# mainBoardV1.net
KiCad netlist of a schematic drawn in EAGLE
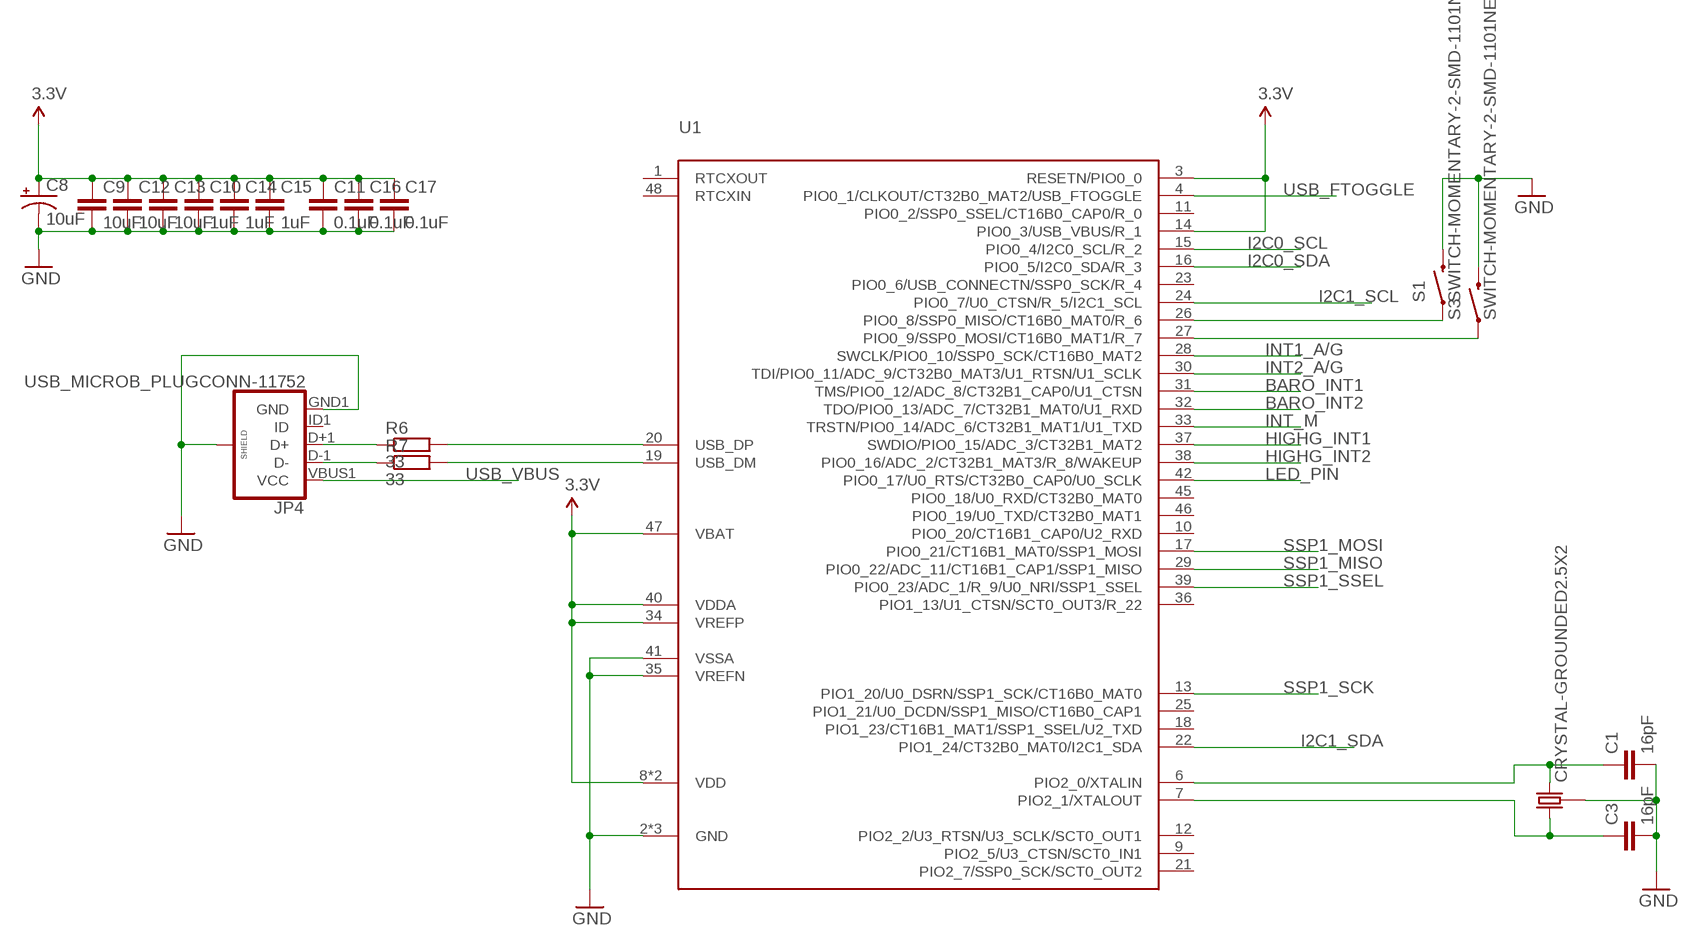
[diagram p0: schematic, sheet 1]
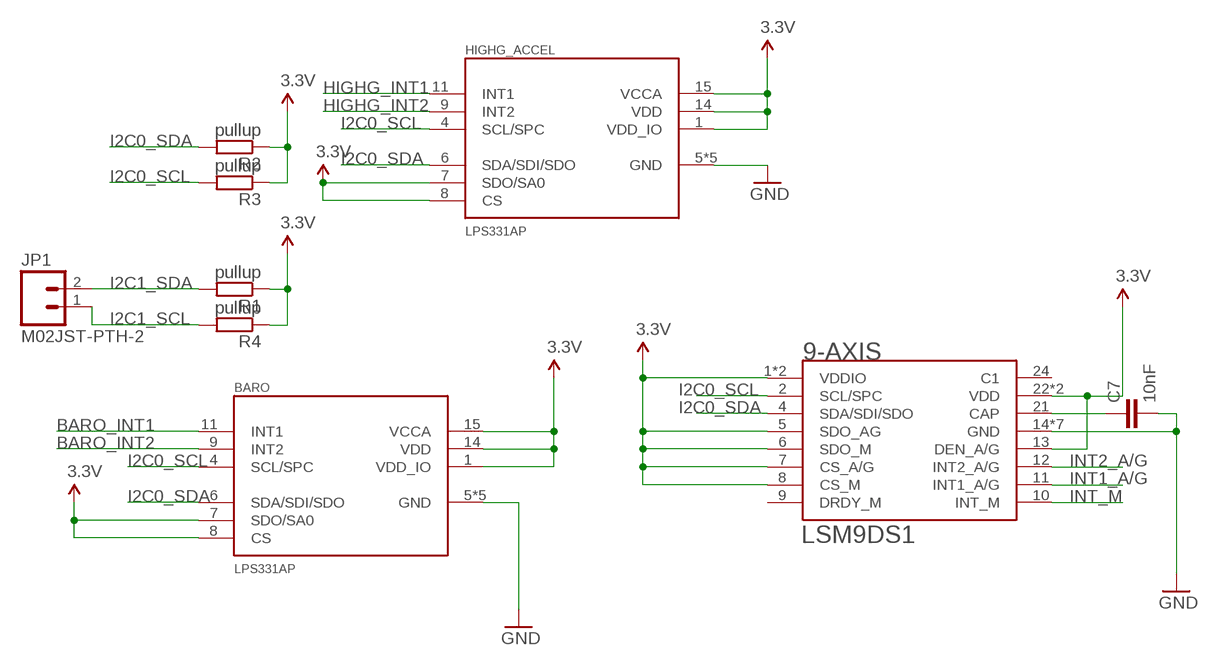
[diagram p1: schematic, sheet 2]
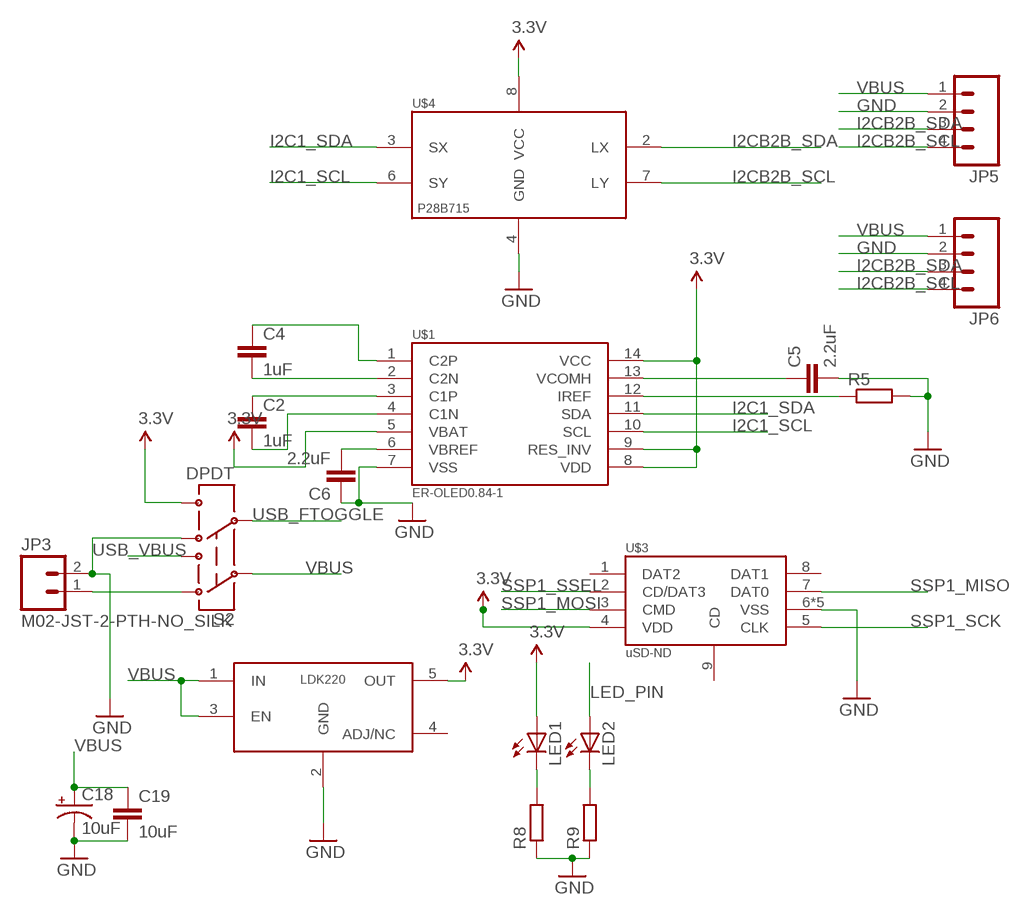
[diagram p2: schematic, sheet 3]

(export (version "E")
  (design (tool "Eeschema 10.0.6"))
  (components
    (comp (ref "C2")
      (value "1uF")
      (footprint "eagle-import:C0402")
      (libsource (lib "eagle-import") (part "C0402"))
    )
    (comp (ref "C4")
      (value "1uF")
      (footprint "eagle-import:C0402")
      (libsource (lib "eagle-import") (part "C0402"))
    )
    (comp (ref "C5")
      (value "2.2uF")
      (footprint "eagle-import:C0402")
      (libsource (lib "eagle-import") (part "C0402"))
    )
    (comp (ref "C6")
      (value "2.2uF")
      (footprint "eagle-import:C0402")
      (libsource (lib "eagle-import") (part "C0402"))
    )
    (comp (ref "C18")
      (value "10uF")
      (footprint "eagle-import:CT3216")
      (libsource (lib "eagle-import") (part "CPOL1206"))
    )
    (comp (ref "C19")
      (value "10uF")
      (footprint "eagle-import:C0402")
      (libsource (lib "eagle-import") (part "C0402"))
    )
    (comp (ref "JP3")
      (value "M02-JST-2-PTH-NO_SILK")
      (footprint "eagle-import:JST-2-PTH-NS")
      (libsource (lib "eagle-import") (part "M02-JST-2-PTH-NO_SILK"))
    )
    (comp (ref "JP5")
      (value "M04JST")
      (footprint "eagle-import:1X04-1.5MM_JST")
      (libsource (lib "eagle-import") (part "M04JST"))
    )
    (comp (ref "JP6")
      (value "M04JST")
      (footprint "eagle-import:1X04-1.5MM_JST")
      (libsource (lib "eagle-import") (part "M04JST"))
    )
    (comp (ref "LED1")
      (value "LEDCHIPLED_0603")
      (footprint "eagle-import:CHIPLED_0603")
      (libsource (lib "eagle-import") (part "LEDCHIPLED_0603"))
    )
    (comp (ref "LED2")
      (value "LEDCHIPLED_0603")
      (footprint "eagle-import:CHIPLED_0603")
      (libsource (lib "eagle-import") (part "LEDCHIPLED_0603"))
    )
    (comp (ref "R5")
      (value "R0402")
      (footprint "eagle-import:R0402")
      (libsource (lib "eagle-import") (part "R0402"))
    )
    (comp (ref "R8")
      (value "R0402")
      (footprint "eagle-import:R0402")
      (libsource (lib "eagle-import") (part "R0402"))
    )
    (comp (ref "R9")
      (value "R0402")
      (footprint "eagle-import:R0402")
      (libsource (lib "eagle-import") (part "R0402"))
    )
    (comp (ref "S2")
      (value "DPDT")
      (footprint "eagle-import:AYZ0202")
      (libsource (lib "eagle-import") (part "SWITCH-DPDTAYZ0202"))
    )
    (comp (ref "U$1")
      (value "ER-OLED0.84-1")
      (footprint "eagle-import:MOLEX_52892-1433")
      (libsource (lib "eagle-import") (part "ER-OLED0.84-1"))
    )
    (comp (ref "U$2")
      (value "LDK220M33R")
      (footprint "eagle-import:SOT23-5")
      (libsource (lib "eagle-import") (part "LDK220M33R"))
    )
    (comp (ref "U$3")
      (value "MICROSD-CD")
      (footprint "eagle-import:MOLEX_SD-47352-101")
      (libsource (lib "eagle-import") (part "MICROSD-CD"))
    )
    (comp (ref "U$4")
      (value "P82B715")
      (footprint "eagle-import:SO8")
      (libsource (lib "eagle-import") (part "P82B715"))
    )
    (comp (ref "9-AXIS")
      (value "LSM9DS1")
      (footprint "eagle-import:LGA-24L-3.5X3X1")
      (libsource (lib "eagle-import") (part "LSM9DS1"))
    )
    (comp (ref "BARO")
      (value "LPS331AP")
      (footprint "eagle-import:LGA-16-3X3X1")
      (libsource (lib "eagle-import") (part "LPS331AP"))
    )
    (comp (ref "C7")
      (value "10nF")
      (footprint "eagle-import:C0402")
      (libsource (lib "eagle-import") (part "C0402"))
    )
    (comp (ref "HIGHG_ACCEL")
      (value "LPS331AP")
      (footprint "eagle-import:LGA-16-3X3X1")
      (libsource (lib "eagle-import") (part "LPS331AP"))
    )
    (comp (ref "JP1")
      (value "M02JST-PTH-2")
      (footprint "eagle-import:JST-2-PTH")
      (libsource (lib "eagle-import") (part "M02JST-PTH-2"))
    )
    (comp (ref "R1")
      (value "pullup")
      (footprint "eagle-import:R0402")
      (libsource (lib "eagle-import") (part "R0402"))
    )
    (comp (ref "R2")
      (value "pullup")
      (footprint "eagle-import:R0402")
      (libsource (lib "eagle-import") (part "R0402"))
    )
    (comp (ref "R3")
      (value "pullup")
      (footprint "eagle-import:R0402")
      (libsource (lib "eagle-import") (part "R0402"))
    )
    (comp (ref "R4")
      (value "pullup")
      (footprint "eagle-import:R0402")
      (libsource (lib "eagle-import") (part "R0402"))
    )
    (comp (ref "C1")
      (value "16pF")
      (footprint "eagle-import:C0402")
      (libsource (lib "eagle-import") (part "C0402"))
    )
    (comp (ref "C3")
      (value "16pF")
      (footprint "eagle-import:C0402")
      (libsource (lib "eagle-import") (part "C0402"))
    )
    (comp (ref "C8")
      (value "10uF")
      (footprint "eagle-import:CT3216")
      (libsource (lib "eagle-import") (part "CPOL1206"))
    )
    (comp (ref "C9")
      (value "10uF")
      (footprint "eagle-import:C0402")
      (libsource (lib "eagle-import") (part "C0402"))
    )
    (comp (ref "C10")
      (value "1uF")
      (footprint "eagle-import:C0402")
      (libsource (lib "eagle-import") (part "C0402"))
    )
    (comp (ref "C11")
      (value "0.1uF")
      (footprint "eagle-import:C0402")
      (libsource (lib "eagle-import") (part "C0402"))
    )
    (comp (ref "C12")
      (value "10uF")
      (footprint "eagle-import:C0402")
      (libsource (lib "eagle-import") (part "C0402"))
    )
    (comp (ref "C13")
      (value "10uF")
      (footprint "eagle-import:C0402")
      (libsource (lib "eagle-import") (part "C0402"))
    )
    (comp (ref "C14")
      (value "1uF")
      (footprint "eagle-import:C0402")
      (libsource (lib "eagle-import") (part "C0402"))
    )
    (comp (ref "C15")
      (value "1uF")
      (footprint "eagle-import:C0402")
      (libsource (lib "eagle-import") (part "C0402"))
    )
    (comp (ref "C16")
      (value "0.1uF")
      (footprint "eagle-import:C0402")
      (libsource (lib "eagle-import") (part "C0402"))
    )
    (comp (ref "C17")
      (value "0.1uF")
      (footprint "eagle-import:C0402")
      (libsource (lib "eagle-import") (part "C0402"))
    )
    (comp (ref "JP4")
      (value "USB_MICROB_PLUGCONN-11752")
      (footprint "eagle-import:USB-B-MICRO-SMD_V03")
      (libsource (lib "eagle-import") (part "USB_MICROB_PLUGCONN-11752"))
    )
    (comp (ref "R6")
      (value "33")
      (footprint "eagle-import:R0402")
      (libsource (lib "eagle-import") (part "R0402"))
    )
    (comp (ref "R7")
      (value "33")
      (footprint "eagle-import:R0402")
      (libsource (lib "eagle-import") (part "R0402"))
    )
    (comp (ref "S1")
      (value "SWITCH-MOMENTARY-2-SMD-1101NE")
      (footprint "eagle-import:TACTILE-SWITCH-1101NE")
      (libsource (lib "eagle-import") (part "SWITCH-MOMENTARY-2-SMD-1101NE"))
    )
    (comp (ref "S3")
      (value "SWITCH-MOMENTARY-2-SMD-1101NE")
      (footprint "eagle-import:TACTILE-SWITCH-1101NE")
      (libsource (lib "eagle-import") (part "SWITCH-MOMENTARY-2-SMD-1101NE"))
    )
    (comp (ref "U$5")
      (value "CRYSTAL-GROUNDED2.5X2")
      (footprint "eagle-import:CRYSTAL-SMD-2.5X2")
      (libsource (lib "eagle-import") (part "CRYSTAL-GROUNDED2.5X2"))
    )
    (comp (ref "U1")
      (value "LPC11U68JBD48")
      (footprint "eagle-import:LQFP48")
      (libsource (lib "eagle-import") (part "LPC11U68JBD48"))
    )
  )
  (nets
    (net (code "1") (name "3.3V") (class "Default")
      (node (ref "9-AXIS") (pin "1") (pinfunction "VDDIO_1") (pintype "bidirectional"))
      (node (ref "9-AXIS") (pin "13") (pinfunction "DEN_A/G_13") (pintype "bidirectional"))
      (node (ref "9-AXIS") (pin "22") (pinfunction "VDD_22") (pintype "bidirectional"))
      (node (ref "9-AXIS") (pin "23") (pinfunction "VDD_23") (pintype "bidirectional"))
      (node (ref "9-AXIS") (pin "3") (pinfunction "VDDIO_3") (pintype "bidirectional"))
      (node (ref "9-AXIS") (pin "5") (pinfunction "SDO_AG_5") (pintype "bidirectional"))
      (node (ref "9-AXIS") (pin "6") (pinfunction "SDO_M_6") (pintype "bidirectional"))
      (node (ref "9-AXIS") (pin "7") (pinfunction "CS_A/G_7") (pintype "bidirectional"))
      (node (ref "9-AXIS") (pin "8") (pinfunction "CS_M_8") (pintype "bidirectional"))
      (node (ref "BARO") (pin "1") (pinfunction "VDD_IO_1") (pintype "bidirectional"))
      (node (ref "BARO") (pin "14") (pinfunction "VDD_14") (pintype "bidirectional"))
      (node (ref "BARO") (pin "15") (pinfunction "VCCA_15") (pintype "bidirectional"))
      (node (ref "BARO") (pin "7") (pinfunction "SDO/SA0_7") (pintype "bidirectional"))
      (node (ref "BARO") (pin "8") (pinfunction "CS_8") (pintype "bidirectional"))
      (node (ref "C10") (pin "1") (pinfunction "1_1") (pintype "passive"))
      (node (ref "C11") (pin "1") (pinfunction "1_1") (pintype "passive"))
      (node (ref "C12") (pin "1") (pinfunction "1_1") (pintype "passive"))
      (node (ref "C13") (pin "1") (pinfunction "1_1") (pintype "passive"))
      (node (ref "C14") (pin "1") (pinfunction "1_1") (pintype "passive"))
      (node (ref "C15") (pin "1") (pinfunction "1_1") (pintype "passive"))
      (node (ref "C16") (pin "1") (pinfunction "1_1") (pintype "passive"))
      (node (ref "C17") (pin "1") (pinfunction "1_1") (pintype "passive"))
      (node (ref "C8") (pin "A") (pinfunction "+_A") (pintype "passive"))
      (node (ref "C9") (pin "1") (pinfunction "1_1") (pintype "passive"))
      (node (ref "HIGHG_ACCEL") (pin "1") (pinfunction "VDD_IO_1") (pintype "bidirectional"))
      (node (ref "HIGHG_ACCEL") (pin "14") (pinfunction "VDD_14") (pintype "bidirectional"))
      (node (ref "HIGHG_ACCEL") (pin "15") (pinfunction "VCCA_15") (pintype "bidirectional"))
      (node (ref "HIGHG_ACCEL") (pin "7") (pinfunction "SDO/SA0_7") (pintype "bidirectional"))
      (node (ref "HIGHG_ACCEL") (pin "8") (pinfunction "CS_8") (pintype "bidirectional"))
      (node (ref "LED1") (pin "A") (pinfunction "A_A") (pintype "passive"))
      (node (ref "R1") (pin "1") (pinfunction "1_1") (pintype "passive"))
      (node (ref "R2") (pin "1") (pinfunction "1_1") (pintype "passive"))
      (node (ref "R3") (pin "1") (pinfunction "1_1") (pintype "passive"))
      (node (ref "R4") (pin "1") (pinfunction "1_1") (pintype "passive"))
      (node (ref "S2") (pin "6") (pinfunction "6_6") (pintype "bidirectional"))
      (node (ref "U$1") (pin "14") (pinfunction "VCC_14") (pintype "bidirectional"))
      (node (ref "U$1") (pin "5") (pinfunction "VBAT_5") (pintype "bidirectional"))
      (node (ref "U$1") (pin "8") (pinfunction "VDD_8") (pintype "bidirectional"))
      (node (ref "U$1") (pin "9") (pinfunction "RES_INV_9") (pintype "bidirectional"))
      (node (ref "U$2") (pin "5") (pinfunction "OUT_5") (pintype "bidirectional"))
      (node (ref "U$3") (pin "4") (pinfunction "VDD_4") (pintype "bidirectional"))
      (node (ref "U$4") (pin "8") (pinfunction "VCC_8") (pintype "bidirectional"))
      (node (ref "U1") (pin "14") (pinfunction "PIO0_3/USB_VBUS/R_1_14") (pintype "bidirectional"))
      (node (ref "U1") (pin "3") (pinfunction "RESETN/PIO0_0_3") (pintype "bidirectional"))
      (node (ref "U1") (pin "34") (pinfunction "VREFP_34") (pintype "bidirectional"))
      (node (ref "U1") (pin "40") (pinfunction "VDDA_40") (pintype "bidirectional"))
      (node (ref "U1") (pin "44") (pinfunction "VDD_44") (pintype "bidirectional"))
      (node (ref "U1") (pin "47") (pinfunction "VBAT_47") (pintype "bidirectional"))
      (node (ref "U1") (pin "8") (pinfunction "VDD_8") (pintype "bidirectional"))
    )
    (net (code "2") (name "BARO_INT1") (class "Default")
      (node (ref "BARO") (pin "11") (pinfunction "INT1_11") (pintype "bidirectional"))
      (node (ref "U1") (pin "31") (pinfunction "TMS/PIO0_12/ADC_8/CT32B1_CAP0/U1_CTSN_31") (pintype "bidirectional"))
    )
    (net (code "3") (name "BARO_INT2") (class "Default")
      (node (ref "BARO") (pin "9") (pinfunction "INT2_9") (pintype "bidirectional"))
      (node (ref "U1") (pin "32") (pinfunction "TDO/PIO0_13/ADC_7/CT32B1_MAT0/U1_RXD_32") (pintype "bidirectional"))
    )
    (net (code "4") (name "GND") (class "Default")
      (node (ref "9-AXIS") (pin "14") (pinfunction "GND_14") (pintype "bidirectional"))
      (node (ref "9-AXIS") (pin "15") (pinfunction "GND_15") (pintype "bidirectional"))
      (node (ref "9-AXIS") (pin "16") (pinfunction "GND_16") (pintype "bidirectional"))
      (node (ref "9-AXIS") (pin "17") (pinfunction "GND_17") (pintype "bidirectional"))
      (node (ref "9-AXIS") (pin "18") (pinfunction "GND_18") (pintype "bidirectional"))
      (node (ref "9-AXIS") (pin "19") (pinfunction "GND_19") (pintype "bidirectional"))
      (node (ref "9-AXIS") (pin "20") (pinfunction "GND_20") (pintype "bidirectional"))
      (node (ref "BARO") (pin "10") (pinfunction "GND_10") (pintype "bidirectional"))
      (node (ref "BARO") (pin "12") (pinfunction "GND_12") (pintype "bidirectional"))
      (node (ref "BARO") (pin "13") (pinfunction "GND_13") (pintype "bidirectional"))
      (node (ref "BARO") (pin "16") (pinfunction "GND_16") (pintype "bidirectional"))
      (node (ref "BARO") (pin "5") (pinfunction "GND_5") (pintype "bidirectional"))
      (node (ref "C1") (pin "2") (pinfunction "2_2") (pintype "passive"))
      (node (ref "C10") (pin "2") (pinfunction "2_2") (pintype "passive"))
      (node (ref "C11") (pin "2") (pinfunction "2_2") (pintype "passive"))
      (node (ref "C12") (pin "2") (pinfunction "2_2") (pintype "passive"))
      (node (ref "C13") (pin "2") (pinfunction "2_2") (pintype "passive"))
      (node (ref "C14") (pin "2") (pinfunction "2_2") (pintype "passive"))
      (node (ref "C15") (pin "2") (pinfunction "2_2") (pintype "passive"))
      (node (ref "C16") (pin "2") (pinfunction "2_2") (pintype "passive"))
      (node (ref "C17") (pin "2") (pinfunction "2_2") (pintype "passive"))
      (node (ref "C18") (pin "C") (pinfunction "-_C") (pintype "passive"))
      (node (ref "C19") (pin "2") (pinfunction "2_2") (pintype "passive"))
      (node (ref "C3") (pin "2") (pinfunction "2_2") (pintype "passive"))
      (node (ref "C5") (pin "2") (pinfunction "2_2") (pintype "passive"))
      (node (ref "C6") (pin "1") (pinfunction "1_1") (pintype "passive"))
      (node (ref "C7") (pin "2") (pinfunction "2_2") (pintype "passive"))
      (node (ref "C8") (pin "C") (pinfunction "-_C") (pintype "passive"))
      (node (ref "C9") (pin "2") (pinfunction "2_2") (pintype "passive"))
      (node (ref "HIGHG_ACCEL") (pin "10") (pinfunction "GND_10") (pintype "bidirectional"))
      (node (ref "HIGHG_ACCEL") (pin "12") (pinfunction "GND_12") (pintype "bidirectional"))
      (node (ref "HIGHG_ACCEL") (pin "13") (pinfunction "GND_13") (pintype "bidirectional"))
      (node (ref "HIGHG_ACCEL") (pin "16") (pinfunction "GND_16") (pintype "bidirectional"))
      (node (ref "HIGHG_ACCEL") (pin "5") (pinfunction "GND_5") (pintype "bidirectional"))
      (node (ref "JP3") (pin "2") (pinfunction "2_2") (pintype "passive"))
      (node (ref "JP4") (pin "GND1") (pinfunction "GND_GND1") (pintype "bidirectional"))
      (node (ref "JP4") (pin "SHIELD1") (pinfunction "SHIELD_SHIELD1") (pintype "bidirectional"))
      (node (ref "JP4") (pin "SHIELD2") (pinfunction "SHIELD_SHIELD2") (pintype "bidirectional"))
      (node (ref "JP4") (pin "SHIELD3") (pinfunction "SHIELD_SHIELD3") (pintype "bidirectional"))
      (node (ref "JP5") (pin "2") (pinfunction "2_2") (pintype "passive"))
      (node (ref "JP6") (pin "2") (pinfunction "2_2") (pintype "passive"))
      (node (ref "R5") (pin "2") (pinfunction "2_2") (pintype "passive"))
      (node (ref "R8") (pin "1") (pinfunction "1_1") (pintype "passive"))
      (node (ref "R9") (pin "1") (pinfunction "1_1") (pintype "passive"))
      (node (ref "S1") (pin "2") (pinfunction "2_2") (pintype "passive"))
      (node (ref "S2") (pin "4") (pinfunction "4_4") (pintype "bidirectional"))
      (node (ref "S3") (pin "2") (pinfunction "2_2") (pintype "passive"))
      (node (ref "U$1") (pin "7") (pinfunction "VSS_7") (pintype "bidirectional"))
      (node (ref "U$2") (pin "2") (pinfunction "GND_2") (pintype "bidirectional"))
      (node (ref "U$3") (pin "6") (pinfunction "VSS_6") (pintype "bidirectional"))
      (node (ref "U$3") (pin "G1") (pinfunction "VSS_G1") (pintype "bidirectional"))
      (node (ref "U$3") (pin "G2") (pinfunction "VSS_G2") (pintype "bidirectional"))
      (node (ref "U$3") (pin "G3") (pinfunction "VSS_G3") (pintype "bidirectional"))
      (node (ref "U$3") (pin "G4") (pinfunction "VSS_G4") (pintype "bidirectional"))
      (node (ref "U$4") (pin "4") (pinfunction "GND_4") (pintype "bidirectional"))
      (node (ref "U$5") (pin "GND1") (pinfunction "3_GND1") (pintype "passive"))
      (node (ref "U$5") (pin "GND2") (pinfunction "3_GND2") (pintype "passive"))
      (node (ref "U1") (pin "2") (pinfunction "GND_2") (pintype "bidirectional"))
      (node (ref "U1") (pin "35") (pinfunction "VREFN_35") (pintype "bidirectional"))
      (node (ref "U1") (pin "41") (pinfunction "VSSA_41") (pintype "bidirectional"))
      (node (ref "U1") (pin "43") (pinfunction "GND_43") (pintype "bidirectional"))
      (node (ref "U1") (pin "5") (pinfunction "GND_5") (pintype "bidirectional"))
    )
    (net (code "5") (name "HIGHG_INT1") (class "Default")
      (node (ref "HIGHG_ACCEL") (pin "11") (pinfunction "INT1_11") (pintype "bidirectional"))
      (node (ref "U1") (pin "37") (pinfunction "SWDIO/PIO0_15/ADC_3/CT32B1_MAT2_37") (pintype "bidirectional"))
    )
    (net (code "6") (name "HIGHG_INT2") (class "Default")
      (node (ref "HIGHG_ACCEL") (pin "9") (pinfunction "INT2_9") (pintype "bidirectional"))
      (node (ref "U1") (pin "38") (pinfunction "PIO0_16/ADC_2/CT32B1_MAT3/R_8/WAKEUP_38") (pintype "bidirectional"))
    )
    (net (code "7") (name "I2C0_SCL") (class "Default")
      (node (ref "9-AXIS") (pin "2") (pinfunction "SCL/SPC_2") (pintype "bidirectional"))
      (node (ref "BARO") (pin "4") (pinfunction "SCL/SPC_4") (pintype "bidirectional"))
      (node (ref "HIGHG_ACCEL") (pin "4") (pinfunction "SCL/SPC_4") (pintype "bidirectional"))
      (node (ref "R3") (pin "2") (pinfunction "2_2") (pintype "passive"))
      (node (ref "U1") (pin "15") (pinfunction "PIO0_4/I2C0_SCL/R_2_15") (pintype "bidirectional"))
    )
    (net (code "8") (name "I2C0_SDA") (class "Default")
      (node (ref "9-AXIS") (pin "4") (pinfunction "SDA/SDI/SDO_4") (pintype "bidirectional"))
      (node (ref "BARO") (pin "6") (pinfunction "SDA/SDI/SDO_6") (pintype "bidirectional"))
      (node (ref "HIGHG_ACCEL") (pin "6") (pinfunction "SDA/SDI/SDO_6") (pintype "bidirectional"))
      (node (ref "R2") (pin "2") (pinfunction "2_2") (pintype "passive"))
      (node (ref "U1") (pin "16") (pinfunction "PIO0_5/I2C0_SDA/R_3_16") (pintype "bidirectional"))
    )
    (net (code "9") (name "I2C1_SCL") (class "Default")
      (node (ref "JP1") (pin "1") (pinfunction "1_1") (pintype "passive"))
      (node (ref "R4") (pin "2") (pinfunction "2_2") (pintype "passive"))
      (node (ref "U$1") (pin "10") (pinfunction "SCL_10") (pintype "bidirectional"))
      (node (ref "U$4") (pin "6") (pinfunction "SY_6") (pintype "bidirectional"))
      (node (ref "U1") (pin "24") (pinfunction "PIO0_7/U0_CTSN/R_5/I2C1_SCL_24") (pintype "bidirectional"))
    )
    (net (code "10") (name "I2C1_SDA") (class "Default")
      (node (ref "JP1") (pin "2") (pinfunction "2_2") (pintype "passive"))
      (node (ref "R1") (pin "2") (pinfunction "2_2") (pintype "passive"))
      (node (ref "U$1") (pin "11") (pinfunction "SDA_11") (pintype "bidirectional"))
      (node (ref "U$4") (pin "3") (pinfunction "SX_3") (pintype "bidirectional"))
      (node (ref "U1") (pin "22") (pinfunction "PIO1_24/CT32B0_MAT0/I2C1_SDA_22") (pintype "bidirectional"))
    )
    (net (code "11") (name "I2CB2B_SCL") (class "Default")
      (node (ref "JP5") (pin "4") (pinfunction "4_4") (pintype "passive"))
      (node (ref "JP6") (pin "4") (pinfunction "4_4") (pintype "passive"))
      (node (ref "U$4") (pin "7") (pinfunction "LY_7") (pintype "bidirectional"))
    )
    (net (code "12") (name "I2CB2B_SDA") (class "Default")
      (node (ref "JP5") (pin "3") (pinfunction "3_3") (pintype "passive"))
      (node (ref "JP6") (pin "3") (pinfunction "3_3") (pintype "passive"))
      (node (ref "U$4") (pin "2") (pinfunction "LX_2") (pintype "bidirectional"))
    )
    (net (code "13") (name "INT1_A{slash}G") (class "Default")
      (node (ref "9-AXIS") (pin "11") (pinfunction "INT1_A/G_11") (pintype "bidirectional"))
      (node (ref "U1") (pin "28") (pinfunction "SWCLK/PIO0_10/SSP0_SCK/CT16B0_MAT2_28") (pintype "bidirectional"))
    )
    (net (code "14") (name "INT2_A{slash}G") (class "Default")
      (node (ref "9-AXIS") (pin "12") (pinfunction "INT2_A/G_12") (pintype "bidirectional"))
      (node (ref "U1") (pin "30") (pinfunction "TDI/PIO0_11/ADC_9/CT32B0_MAT3/U1_RTSN/U1_SCLK_30") (pintype "bidirectional"))
    )
    (net (code "15") (name "INT_M") (class "Default")
      (node (ref "9-AXIS") (pin "10") (pinfunction "INT_M_10") (pintype "bidirectional"))
      (node (ref "U1") (pin "33") (pinfunction "TRSTN/PIO0_14/ADC_6/CT32B1_MAT1/U1_TXD_33") (pintype "bidirectional"))
    )
    (net (code "16") (name "LED_PIN") (class "Default")
      (node (ref "LED2") (pin "A") (pinfunction "A_A") (pintype "passive"))
      (node (ref "U1") (pin "42") (pinfunction "PIO0_17/U0_RTS/CT32B0_CAP0/U0_SCLK_42") (pintype "bidirectional"))
    )
    (net (code "17") (name "Net-(9-AXIS-CAP)") (class "Default")
      (node (ref "9-AXIS") (pin "21") (pinfunction "CAP_21") (pintype "bidirectional"))
      (node (ref "C7") (pin "1") (pinfunction "1_1") (pintype "passive"))
    )
    (net (code "18") (name "Net-(JP3-Pad1)") (class "Default")
      (node (ref "JP3") (pin "1") (pinfunction "1_1") (pintype "passive"))
      (node (ref "S2") (pin "1") (pinfunction "1_1") (pintype "bidirectional"))
    )
    (net (code "19") (name "Net-(JP4-D+)") (class "Default")
      (node (ref "JP4") (pin "D+1") (pinfunction "D+_D+1") (pintype "bidirectional"))
      (node (ref "R6") (pin "1") (pinfunction "1_1") (pintype "passive"))
    )
    (net (code "20") (name "Net-(JP4-D-)") (class "Default")
      (node (ref "JP4") (pin "D-1") (pinfunction "D-_D-1") (pintype "bidirectional"))
      (node (ref "R7") (pin "1") (pinfunction "1_1") (pintype "passive"))
    )
    (net (code "21") (name "Net-(LED1-PadC)") (class "Default")
      (node (ref "LED1") (pin "C") (pinfunction "C_C") (pintype "passive"))
      (node (ref "R8") (pin "2") (pinfunction "2_2") (pintype "passive"))
    )
    (net (code "22") (name "Net-(LED2-PadC)") (class "Default")
      (node (ref "LED2") (pin "C") (pinfunction "C_C") (pintype "passive"))
      (node (ref "R9") (pin "2") (pinfunction "2_2") (pintype "passive"))
    )
    (net (code "23") (name "Net-(U$1-C1N)") (class "Default")
      (node (ref "C2") (pin "2") (pinfunction "2_2") (pintype "passive"))
      (node (ref "U$1") (pin "4") (pinfunction "C1N_4") (pintype "bidirectional"))
    )
    (net (code "24") (name "Net-(U$1-C1P)") (class "Default")
      (node (ref "C2") (pin "1") (pinfunction "1_1") (pintype "passive"))
      (node (ref "U$1") (pin "3") (pinfunction "C1P_3") (pintype "bidirectional"))
    )
    (net (code "25") (name "Net-(U$1-C2N)") (class "Default")
      (node (ref "C4") (pin "2") (pinfunction "2_2") (pintype "passive"))
      (node (ref "U$1") (pin "2") (pinfunction "C2N_2") (pintype "bidirectional"))
    )
    (net (code "26") (name "Net-(U$1-C2P)") (class "Default")
      (node (ref "C4") (pin "1") (pinfunction "1_1") (pintype "passive"))
      (node (ref "U$1") (pin "1") (pinfunction "C2P_1") (pintype "bidirectional"))
    )
    (net (code "27") (name "Net-(U$1-IREF)") (class "Default")
      (node (ref "R5") (pin "1") (pinfunction "1_1") (pintype "passive"))
      (node (ref "U$1") (pin "12") (pinfunction "IREF_12") (pintype "bidirectional"))
    )
    (net (code "28") (name "Net-(U$1-VBREF)") (class "Default")
      (node (ref "C6") (pin "2") (pinfunction "2_2") (pintype "passive"))
      (node (ref "U$1") (pin "6") (pinfunction "VBREF_6") (pintype "bidirectional"))
    )
    (net (code "29") (name "Net-(U$1-VCOMH)") (class "Default")
      (node (ref "C5") (pin "1") (pinfunction "1_1") (pintype "passive"))
      (node (ref "U$1") (pin "13") (pinfunction "VCOMH_13") (pintype "bidirectional"))
    )
    (net (code "30") (name "Net-(U$5-1)") (class "Default")
      (node (ref "C3") (pin "1") (pinfunction "1_1") (pintype "passive"))
      (node (ref "U$5") (pin "P1") (pinfunction "1_P1") (pintype "passive"))
      (node (ref "U1") (pin "7") (pinfunction "PIO2_1/XTALOUT_7") (pintype "bidirectional"))
    )
    (net (code "31") (name "Net-(U$5-2)") (class "Default")
      (node (ref "C1") (pin "1") (pinfunction "1_1") (pintype "passive"))
      (node (ref "U$5") (pin "P2") (pinfunction "2_P2") (pintype "passive"))
      (node (ref "U1") (pin "6") (pinfunction "PIO2_0/XTALIN_6") (pintype "bidirectional"))
    )
    (net (code "32") (name "Net-(U1-PIO0_8{slash}SSP0_MISO{slash}CT16B0_MAT0{slash}R_6)") (class "Default")
      (node (ref "S1") (pin "1") (pinfunction "1_1") (pintype "passive"))
      (node (ref "U1") (pin "26") (pinfunction "PIO0_8/SSP0_MISO/CT16B0_MAT0/R_6_26") (pintype "bidirectional"))
    )
    (net (code "33") (name "Net-(U1-PIO0_9{slash}SSP0_MOSI{slash}CT16B0_MAT1{slash}R_7)") (class "Default")
      (node (ref "S3") (pin "1") (pinfunction "1_1") (pintype "passive"))
      (node (ref "U1") (pin "27") (pinfunction "PIO0_9/SSP0_MOSI/CT16B0_MAT1/R_7_27") (pintype "bidirectional"))
    )
    (net (code "34") (name "Net-(U1-USB_DM)") (class "Default")
      (node (ref "R7") (pin "2") (pinfunction "2_2") (pintype "passive"))
      (node (ref "U1") (pin "19") (pinfunction "USB_DM_19") (pintype "bidirectional"))
    )
    (net (code "35") (name "Net-(U1-USB_DP)") (class "Default")
      (node (ref "R6") (pin "2") (pinfunction "2_2") (pintype "passive"))
      (node (ref "U1") (pin "20") (pinfunction "USB_DP_20") (pintype "bidirectional"))
    )
    (net (code "36") (name "SSP1_MISO") (class "Default")
      (node (ref "U$3") (pin "7") (pinfunction "DAT0_7") (pintype "bidirectional"))
      (node (ref "U1") (pin "29") (pinfunction "PIO0_22/ADC_11/CT16B1_CAP1/SSP1_MISO_29") (pintype "bidirectional"))
    )
    (net (code "37") (name "SSP1_MOSI") (class "Default")
      (node (ref "U$3") (pin "3") (pinfunction "CMD_3") (pintype "bidirectional"))
      (node (ref "U1") (pin "17") (pinfunction "PIO0_21/CT16B1_MAT0/SSP1_MOSI_17") (pintype "bidirectional"))
    )
    (net (code "38") (name "SSP1_SCK") (class "Default")
      (node (ref "U$3") (pin "5") (pinfunction "CLK_5") (pintype "bidirectional"))
      (node (ref "U1") (pin "13") (pinfunction "PIO1_20/U0_DSRN/SSP1_SCK/CT16B0_MAT0_13") (pintype "bidirectional"))
    )
    (net (code "39") (name "SSP1_SSEL") (class "Default")
      (node (ref "U$3") (pin "2") (pinfunction "CD/DAT3_2") (pintype "bidirectional"))
      (node (ref "U1") (pin "39") (pinfunction "PIO0_23/ADC_1/R_9/U0_NRI/SSP1_SSEL_39") (pintype "bidirectional"))
    )
    (net (code "40") (name "USB_FTOGGLE") (class "Default")
      (node (ref "S2") (pin "5") (pinfunction "5_5") (pintype "bidirectional"))
      (node (ref "U1") (pin "4") (pinfunction "PIO0_1/CLKOUT/CT32B0_MAT2/USB_FTOGGLE_4") (pintype "bidirectional"))
    )
    (net (code "41") (name "USB_VBUS") (class "Default")
      (node (ref "JP4") (pin "VBUS1") (pinfunction "VCC_VBUS1") (pintype "bidirectional"))
      (node (ref "S2") (pin "3") (pinfunction "3_3") (pintype "bidirectional"))
    )
    (net (code "42") (name "VBUS") (class "Default")
      (node (ref "C18") (pin "A") (pinfunction "+_A") (pintype "passive"))
      (node (ref "C19") (pin "1") (pinfunction "1_1") (pintype "passive"))
      (node (ref "JP5") (pin "1") (pinfunction "1_1") (pintype "passive"))
      (node (ref "JP6") (pin "1") (pinfunction "1_1") (pintype "passive"))
      (node (ref "S2") (pin "2") (pinfunction "2_2") (pintype "bidirectional"))
      (node (ref "U$2") (pin "1") (pinfunction "IN_1") (pintype "bidirectional"))
      (node (ref "U$2") (pin "3") (pinfunction "EN_3") (pintype "bidirectional"))
    )
    (net (code "43") (name "unconnected-(9-AXIS-C1-Pad24)") (class "Default")
      (node (ref "9-AXIS") (pin "24") (pinfunction "C1_24") (pintype "bidirectional"))
    )
    (net (code "44") (name "unconnected-(9-AXIS-DRDY_M-Pad9)") (class "Default")
      (node (ref "9-AXIS") (pin "9") (pinfunction "DRDY_M_9") (pintype "bidirectional"))
    )
    (net (code "45") (name "unconnected-(JP4-ID-PadID1)") (class "Default")
      (node (ref "JP4") (pin "ID1") (pinfunction "ID_ID1") (pintype "bidirectional"))
    )
    (net (code "46") (name "unconnected-(U$2-ADJ{slash}NC-Pad4)") (class "Default")
      (node (ref "U$2") (pin "4") (pinfunction "ADJ/NC_4") (pintype "bidirectional"))
    )
    (net (code "47") (name "unconnected-(U$3-CD-Pad9)") (class "Default")
      (node (ref "U$3") (pin "9") (pinfunction "CD_9") (pintype "bidirectional"))
    )
    (net (code "48") (name "unconnected-(U$3-DAT1-Pad8)") (class "Default")
      (node (ref "U$3") (pin "8") (pinfunction "DAT1_8") (pintype "bidirectional"))
    )
    (net (code "49") (name "unconnected-(U$3-DAT2-Pad1)") (class "Default")
      (node (ref "U$3") (pin "1") (pinfunction "DAT2_1") (pintype "bidirectional"))
    )
    (net (code "50") (name "unconnected-(U1-PIO0_2{slash}SSP0_SSEL{slash}CT16B0_CAP0{slash}R_0-Pad11)") (class "Default")
      (node (ref "U1") (pin "11") (pinfunction "PIO0_2/SSP0_SSEL/CT16B0_CAP0/R_0_11") (pintype "bidirectional"))
    )
    (net (code "51") (name "unconnected-(U1-PIO0_6{slash}USB_CONNECTN{slash}SSP0_SCK{slash}R_4-Pad23)") (class "Default")
      (node (ref "U1") (pin "23") (pinfunction "PIO0_6/USB_CONNECTN/SSP0_SCK/R_4_23") (pintype "bidirectional"))
    )
    (net (code "52") (name "unconnected-(U1-PIO0_18{slash}U0_RXD{slash}CT32B0_MAT0-Pad45)") (class "Default")
      (node (ref "U1") (pin "45") (pinfunction "PIO0_18/U0_RXD/CT32B0_MAT0_45") (pintype "bidirectional"))
    )
    (net (code "53") (name "unconnected-(U1-PIO0_19{slash}U0_TXD{slash}CT32B0_MAT1-Pad46)") (class "Default")
      (node (ref "U1") (pin "46") (pinfunction "PIO0_19/U0_TXD/CT32B0_MAT1_46") (pintype "bidirectional"))
    )
    (net (code "54") (name "unconnected-(U1-PIO0_20{slash}CT16B1_CAP0{slash}U2_RXD-Pad10)") (class "Default")
      (node (ref "U1") (pin "10") (pinfunction "PIO0_20/CT16B1_CAP0/U2_RXD_10") (pintype "bidirectional"))
    )
    (net (code "55") (name "unconnected-(U1-PIO1_13{slash}U1_CTSN{slash}SCT0_OUT3{slash}R_22-Pad36)") (class "Default")
      (node (ref "U1") (pin "36") (pinfunction "PIO1_13/U1_CTSN/SCT0_OUT3/R_22_36") (pintype "bidirectional"))
    )
    (net (code "56") (name "unconnected-(U1-PIO1_21{slash}U0_DCDN{slash}SSP1_MISO{slash}CT16B0_CAP1-Pad25)") (class "Default")
      (node (ref "U1") (pin "25") (pinfunction "PIO1_21/U0_DCDN/SSP1_MISO/CT16B0_CAP1_25") (pintype "bidirectional"))
    )
    (net (code "57") (name "unconnected-(U1-PIO1_23{slash}CT16B1_MAT1{slash}SSP1_SSEL{slash}U2_TXD-Pad18)") (class "Default")
      (node (ref "U1") (pin "18") (pinfunction "PIO1_23/CT16B1_MAT1/SSP1_SSEL/U2_TXD_18") (pintype "bidirectional"))
    )
    (net (code "58") (name "unconnected-(U1-PIO2_2{slash}U3_RTSN{slash}U3_SCLK{slash}SCT0_OUT1-Pad12)") (class "Default")
      (node (ref "U1") (pin "12") (pinfunction "PIO2_2/U3_RTSN/U3_SCLK/SCT0_OUT1_12") (pintype "bidirectional"))
    )
    (net (code "59") (name "unconnected-(U1-PIO2_5{slash}U3_CTSN{slash}SCT0_IN1-Pad9)") (class "Default")
      (node (ref "U1") (pin "9") (pinfunction "PIO2_5/U3_CTSN/SCT0_IN1_9") (pintype "bidirectional"))
    )
    (net (code "60") (name "unconnected-(U1-PIO2_7{slash}SSP0_SCK{slash}SCT0_OUT2-Pad21)") (class "Default")
      (node (ref "U1") (pin "21") (pinfunction "PIO2_7/SSP0_SCK/SCT0_OUT2_21") (pintype "bidirectional"))
    )
    (net (code "61") (name "unconnected-(U1-RTCXIN-Pad48)") (class "Default")
      (node (ref "U1") (pin "48") (pinfunction "RTCXIN_48") (pintype "bidirectional"))
    )
    (net (code "62") (name "unconnected-(U1-RTCXOUT-Pad1)") (class "Default")
      (node (ref "U1") (pin "1") (pinfunction "RTCXOUT_1") (pintype "bidirectional"))
    )
  )
)
